# SHDN-BSPD-S09-V00-PSU.net
KiCad netlist of a schematic drawn in Altium Designer
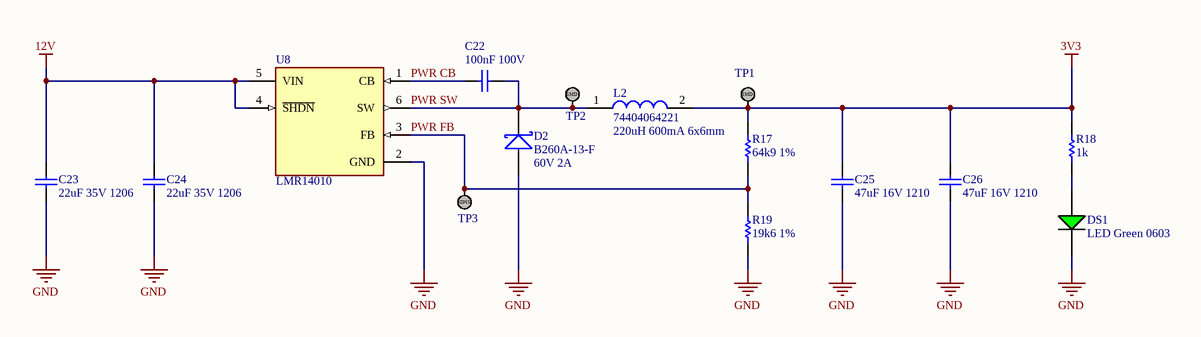
[diagram p0: SHDN-BSPD-S09-V00-PSU.SchDoc]

(export (version "E")
  (design (tool "Eeschema 10.0.6"))
  (components
    (comp (ref "C22")
      (value "100nF 100V")
      (footprint "Cap_Ceramic_0603")
      (description "Capacitor, Ceramic, SMD, 100nF, 100V, 5%, X7R, 0603")
      (libsource (lib "StandardCapacitors") (part "100nF 100V 5% X7R 0603"))
    )
    (comp (ref "C23")
      (value "22uF 35V 1206")
      (footprint "Cap_Ceramic_1206")
      (description "Capacitor, Ceramic, SMD, 22uF, 35V, 10%, X7R, 1206")
      (libsource (lib "StandardCapacitors") (part "22uF 35V 10% X7R 1206"))
    )
    (comp (ref "C24")
      (value "22uF 35V 1206")
      (footprint "Cap_Ceramic_1206")
      (description "Capacitor, Ceramic, SMD, 22uF, 35V, 10%, X7R, 1206")
      (libsource (lib "StandardCapacitors") (part "22uF 35V 10% X7R 1206"))
    )
    (comp (ref "C25")
      (value "47uF 16V 1210")
      (footprint "Cap_Ceramic_1210")
      (description "Capacitor, Ceramic, SMD, 47uF, 16V, 5%, X7R, 1210")
      (libsource (lib "StandardCapacitors") (part "47uF 16V 10% X7R 1210"))
    )
    (comp (ref "C26")
      (value "47uF 16V 1210")
      (footprint "Cap_Ceramic_1210")
      (description "Capacitor, Ceramic, SMD, 47uF, 16V, 5%, X7R, 1210")
      (libsource (lib "StandardCapacitors") (part "47uF 16V 10% X7R 1210"))
    )
    (comp (ref "D2")
      (value "B260A-13-F")
      (footprint "SMA")
      (description "Diode, Schottky Barrier Rectifier, 60 V, 2 A, B260A-13-F")
      (libsource (lib "QUTMS_DiodeLibrary") (part "B260A-13-F"))
    )
    (comp (ref "DS1")
      (value "LED Green 0603")
      (footprint "LED GREEN 0603")
      (libsource (lib "QUTMS_LEDLibrary") (part "LED Green 0603"))
    )
    (comp (ref "L2")
      (value "74404064221")
      (footprint "Inductor_6x6mm")
      (description "FIXED IND 220UH 660MA 850 MOHM")
      (libsource (lib "QUTMS_InductorLibrary") (part "74404064221"))
    )
    (comp (ref "R17")
      (value "64k9 1%")
      (footprint "Res_ThinFilm_0603")
      (description "Resistor, SMD, 64k9, 0.1W, 5%, 0603")
      (libsource (lib "StandardResistors") (part "64k9 1% 0603"))
    )
    (comp (ref "R18")
      (value "1k")
      (footprint "Res_ThinFilm_0603")
      (description "Resistor, SMD, 1k, 0.1W, 5%, 0603")
      (libsource (lib "StandardResistors") (part "1k 5% 0603"))
    )
    (comp (ref "R19")
      (value "19k6 1%")
      (footprint "Res_ThinFilm_0603")
      (description "Resistor, SMD, 19k6, 0.1W, 5%, 0603")
      (libsource (lib "StandardResistors") (part "19k6 1% 0603"))
    )
    (comp (ref "TP1")
      (value "TestPoint_SMD")
      (footprint "TestPointSMD")
      (libsource (lib "StandardTest") (part "TestPoint_SMD"))
    )
    (comp (ref "TP2")
      (value "TestPoint_SMD")
      (footprint "TestPointSMD")
      (libsource (lib "StandardTest") (part "TestPoint_SMD"))
    )
    (comp (ref "TP3")
      (value "TestPoint_SMD")
      (footprint "TestPointSMD")
      (libsource (lib "StandardTest") (part "TestPoint_SMD"))
    )
    (comp (ref "U8")
      (value "LMR14010")
      (footprint "LMR14010")
      (libsource (lib "QUTMS_PowerSupplyLibrary") (part "LMR14010"))
    )
  )
  (nets
    (net (code "1") (name "/PWR CB") (class "Default")
      (node (ref "C22") (pin "1") (pinfunction "1_1") (pintype "passive"))
      (node (ref "U8") (pin "1") (pinfunction "CB_1") (pintype "input"))
    )
    (net (code "2") (name "/PWR FB") (class "Default")
      (node (ref "R17") (pin "1") (pinfunction "1_1") (pintype "passive"))
      (node (ref "R19") (pin "2") (pinfunction "2_2") (pintype "passive"))
      (node (ref "TP3") (pin "1") (pinfunction "1_1") (pintype "passive"))
      (node (ref "U8") (pin "3") (pinfunction "FB_3") (pintype "input"))
    )
    (net (code "3") (name "/PWR SW") (class "Default")
      (node (ref "C22") (pin "2") (pinfunction "2_2") (pintype "passive"))
      (node (ref "D2") (pin "K") (pinfunction "K_K") (pintype "passive"))
      (node (ref "L2") (pin "1") (pinfunction "1_1") (pintype "passive"))
      (node (ref "TP2") (pin "1") (pinfunction "1_1") (pintype "passive"))
      (node (ref "U8") (pin "6") (pinfunction "SW_6") (pintype "output"))
    )
    (net (code "4") (name "3V3") (class "Default")
      (node (ref "C25") (pin "2") (pinfunction "2_2") (pintype "passive"))
      (node (ref "C26") (pin "2") (pinfunction "2_2") (pintype "passive"))
      (node (ref "L2") (pin "2") (pinfunction "2_2") (pintype "passive"))
      (node (ref "R17") (pin "2") (pinfunction "2_2") (pintype "passive"))
      (node (ref "R18") (pin "2") (pinfunction "2_2") (pintype "passive"))
      (node (ref "TP1") (pin "1") (pinfunction "1_1") (pintype "passive"))
    )
    (net (code "5") (name "12V") (class "Default")
      (node (ref "C23") (pin "2") (pinfunction "2_2") (pintype "passive"))
      (node (ref "C24") (pin "2") (pinfunction "2_2") (pintype "passive"))
      (node (ref "U8") (pin "4") (pinfunction "~{SHDN}_4") (pintype "input"))
      (node (ref "U8") (pin "5") (pinfunction "VIN_5") (pintype "power_in"))
    )
    (net (code "6") (name "GND") (class "Default")
      (node (ref "C23") (pin "1") (pinfunction "1_1") (pintype "passive"))
      (node (ref "C24") (pin "1") (pinfunction "1_1") (pintype "passive"))
      (node (ref "C25") (pin "1") (pinfunction "1_1") (pintype "passive"))
      (node (ref "C26") (pin "1") (pinfunction "1_1") (pintype "passive"))
      (node (ref "D2") (pin "A") (pinfunction "A_A") (pintype "passive"))
      (node (ref "DS1") (pin "2") (pinfunction "C_2") (pintype "passive"))
      (node (ref "R19") (pin "1") (pinfunction "1_1") (pintype "passive"))
      (node (ref "U8") (pin "2") (pinfunction "GND_2") (pintype "power_in"))
    )
    (net (code "7") (name "Net-(DS1-A)") (class "Default")
      (node (ref "DS1") (pin "1") (pinfunction "A_1") (pintype "passive"))
      (node (ref "R18") (pin "1") (pinfunction "1_1") (pintype "passive"))
    )
  )
)
